# SSTuino_Evo.net
KiCad netlist of a schematic drawn in EAGLE
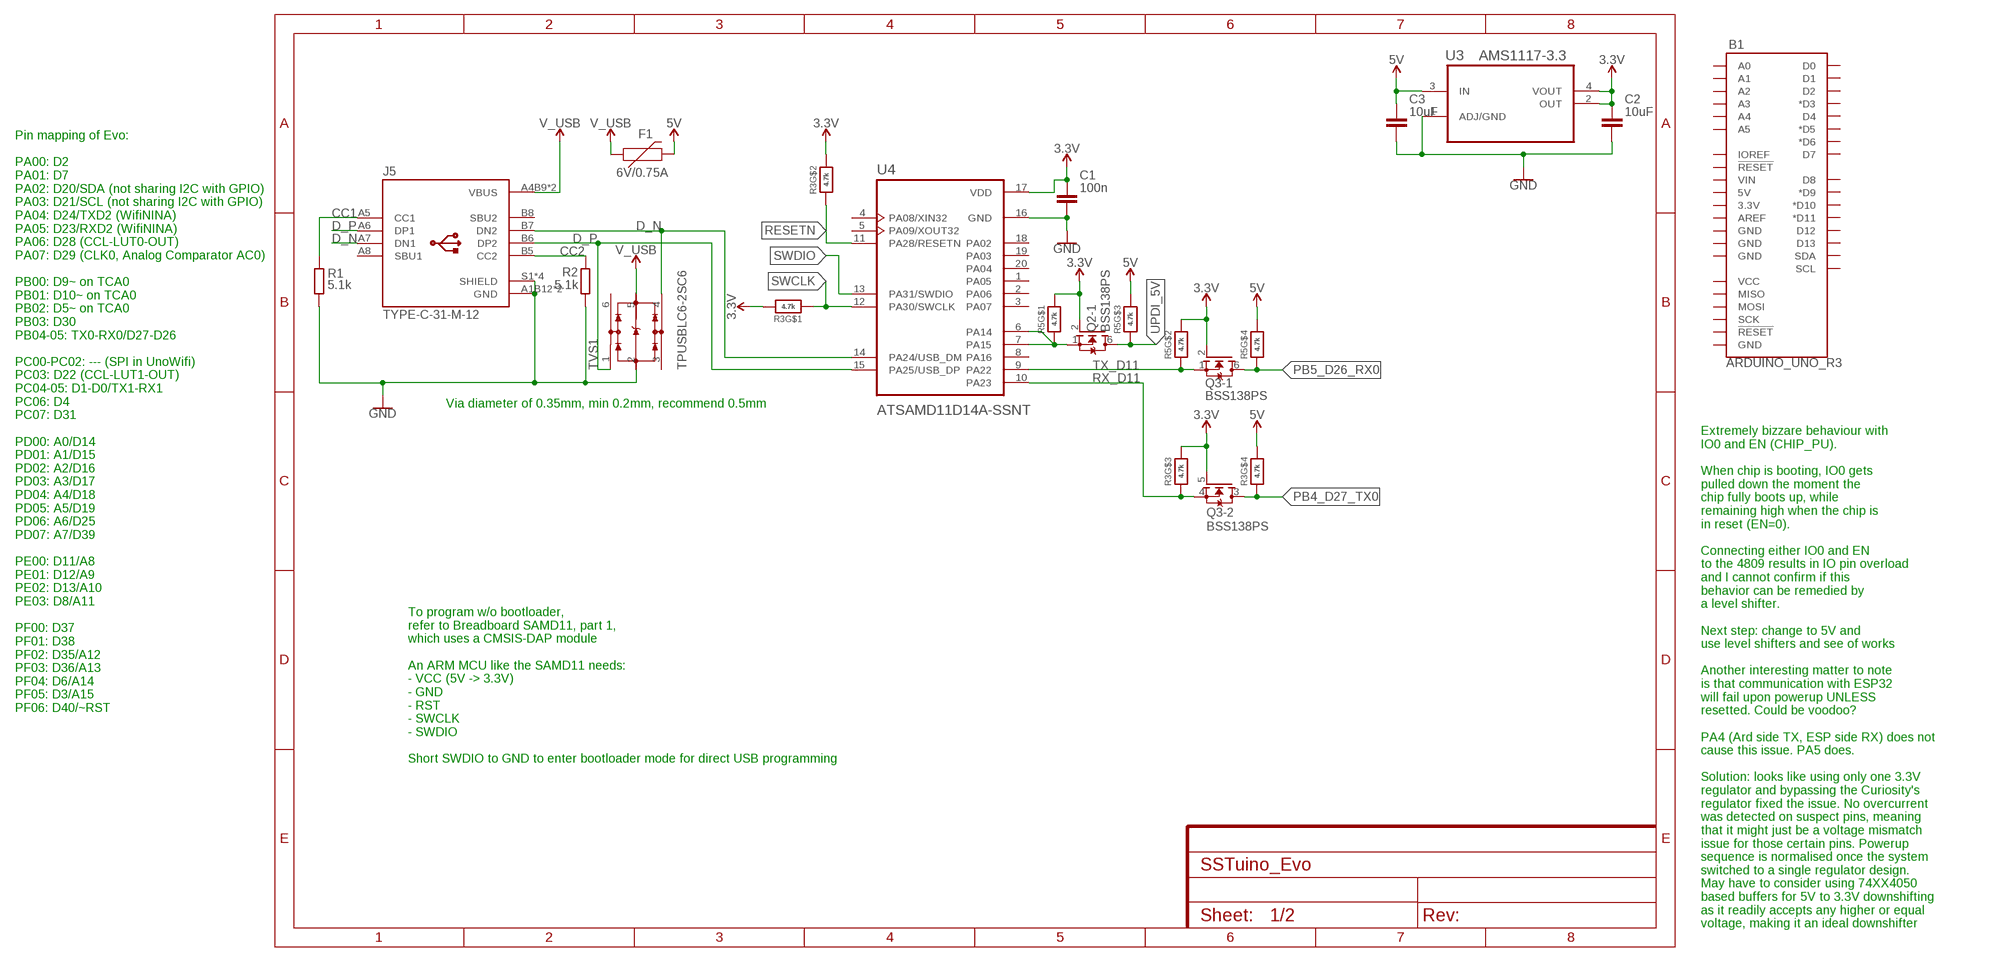
[diagram p0: schematic, sheet 1]
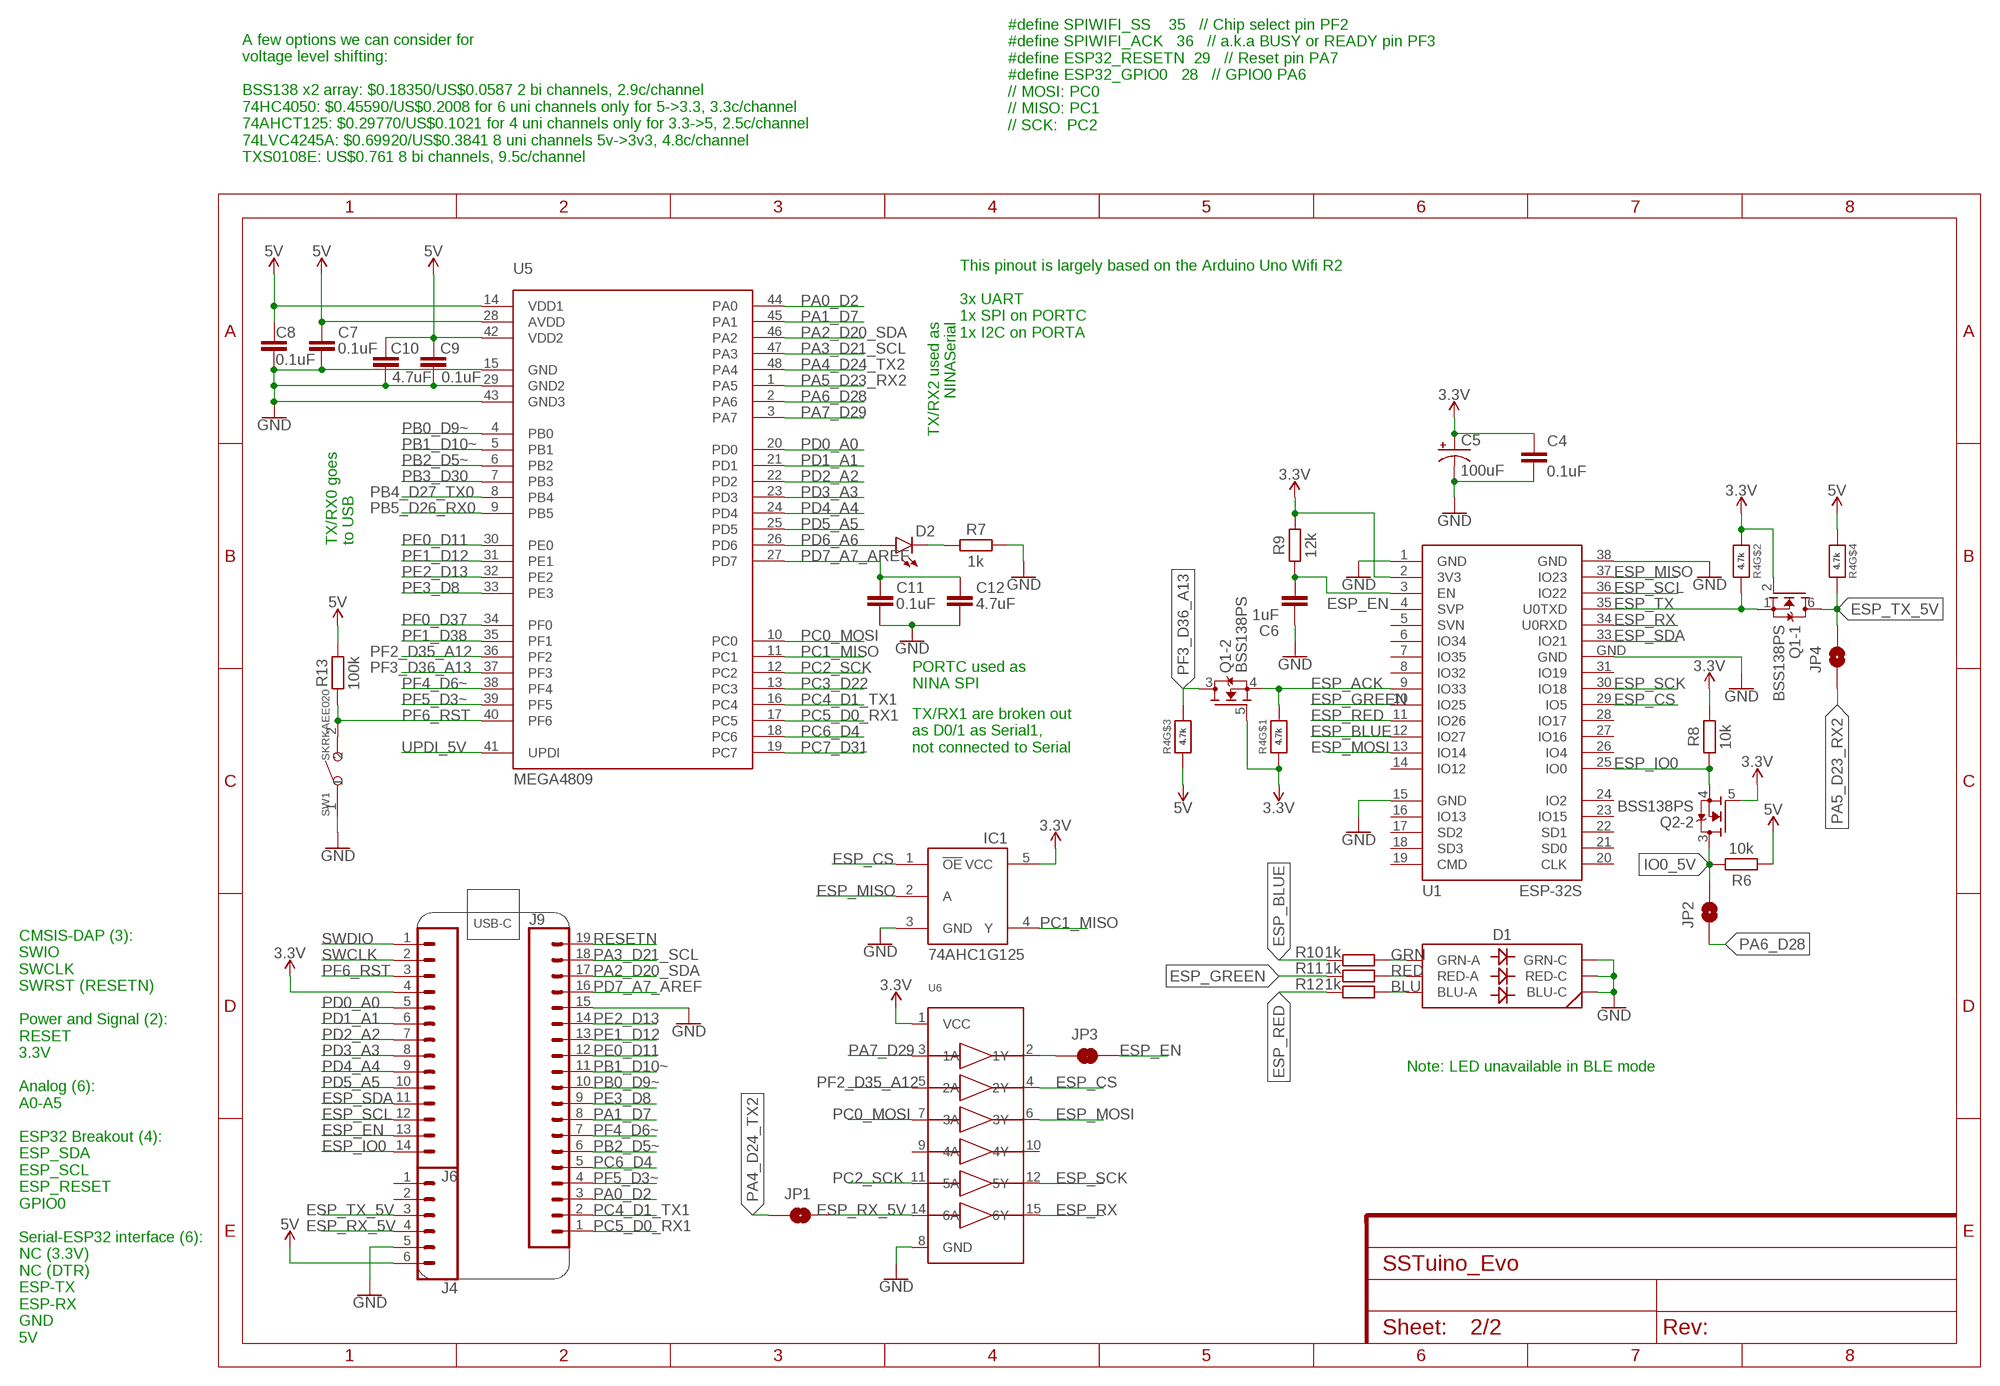
[diagram p1: schematic, sheet 2]

(export (version "E")
  (design (tool "Eeschema 10.0.6"))
  (components
    (comp (ref "C4")
      (value "0.1uF")
      (footprint "eagle-import:CAPC1005X60")
      (libsource (lib "eagle-import") (part "CCHIP-0402(1005-METRIC)_"))
    )
    (comp (ref "C5")
      (value "100uF")
      (footprint "eagle-import:CAPMP3216X180N")
      (libsource (lib "eagle-import") (part "C-POL-USTANTALUM-1206(3216-METRIC)_"))
    )
    (comp (ref "C6")
      (value "1uF")
      (footprint "eagle-import:CAPC1005X60")
      (libsource (lib "eagle-import") (part "CCHIP-0402(1005-METRIC)_"))
    )
    (comp (ref "C7")
      (value "0.1uF")
      (footprint "eagle-import:CAPC1005X60")
      (libsource (lib "eagle-import") (part "CCHIP-0402(1005-METRIC)_"))
    )
    (comp (ref "C8")
      (value "0.1uF")
      (footprint "eagle-import:CAPC1005X60")
      (libsource (lib "eagle-import") (part "CCHIP-0402(1005-METRIC)_"))
    )
    (comp (ref "C9")
      (value "0.1uF")
      (footprint "eagle-import:CAPC1005X60")
      (libsource (lib "eagle-import") (part "CCHIP-0402(1005-METRIC)_"))
    )
    (comp (ref "C10")
      (value "4.7uF")
      (footprint "eagle-import:CAPC1005X60")
      (libsource (lib "eagle-import") (part "CCHIP-0402(1005-METRIC)_"))
    )
    (comp (ref "C11")
      (value "0.1uF")
      (footprint "eagle-import:CAPC1005X60")
      (libsource (lib "eagle-import") (part "CCHIP-0402(1005-METRIC)_"))
    )
    (comp (ref "C12")
      (value "4.7uF")
      (footprint "eagle-import:CAPC1005X60")
      (libsource (lib "eagle-import") (part "CCHIP-0402(1005-METRIC)_"))
    )
    (comp (ref "D1")
      (value "LED-RGBTC5050RGBF08")
      (footprint "eagle-import:LED-TRICOLOR-5050")
      (libsource (lib "eagle-import") (part "LED-RGBTC5050RGBF08"))
    )
    (comp (ref "D2")
      (value "LED0603")
      (footprint "eagle-import:LED-0603")
      (libsource (lib "eagle-import") (part "LED0603"))
    )
    (comp (ref "IC1")
      (value "74AHC1G125")
      (footprint "eagle-import:SOT23-5L")
      (fields (field (name "LCSC_PART") "C124295"))
      (libsource (lib "eagle-import") (part "74AHC1G125"))
    )
    (comp (ref "J4")
      (value "CONN_06NO_SILK_FEMALE_PTH")
      (footprint "eagle-import:1X06_NO_SILK")
      (libsource (lib "eagle-import") (part "CONN_06NO_SILK_FEMALE_PTH"))
    )
    (comp (ref "J6")
      (value "CONN_14NO_SILK")
      (footprint "eagle-import:1X14_NO_SILK")
      (libsource (lib "eagle-import") (part "CONN_14NO_SILK"))
    )
    (comp (ref "J9")
      (value "CONN_191X19_NO_SILK")
      (footprint "eagle-import:1X19_NO_SILK")
      (libsource (lib "eagle-import") (part "CONN_191X19_NO_SILK"))
    )
    (comp (ref "JP1")
      (value "JUMPER-SMT_2_NO_SILK")
      (footprint "eagle-import:SMT-JUMPER_2_NO_SILK")
      (libsource (lib "eagle-import") (part "JUMPER-SMT_2_NO_SILK"))
    )
    (comp (ref "JP2")
      (value "JUMPER-SMT_2_NO_SILK")
      (footprint "eagle-import:SMT-JUMPER_2_NO_SILK")
      (libsource (lib "eagle-import") (part "JUMPER-SMT_2_NO_SILK"))
    )
    (comp (ref "JP3")
      (value "JUMPER-SMT_2_NC_TRACE_SILK")
      (footprint "eagle-import:SMT-JUMPER_2_NC_TRACE_SILK")
      (libsource (lib "eagle-import") (part "JUMPER-SMT_2_NC_TRACE_SILK"))
    )
    (comp (ref "JP4")
      (value "JUMPER-SMT_2_NO_SILK")
      (footprint "eagle-import:SMT-JUMPER_2_NO_SILK")
      (libsource (lib "eagle-import") (part "JUMPER-SMT_2_NO_SILK"))
    )
    (comp (ref "Q1")
      (value "BSS138PS")
      (footprint "eagle-import:ARDUINO-TRANSISTORS_SOT363")
      (fields (field (name "MANUFACTURER") "NXP") (field (name "LCSC_PART") "C193381"))
      (libsource (lib "eagle-import") (part "BSS138PS"))
    )
    (comp (ref "Q2")
      (value "BSS138PS")
      (footprint "eagle-import:ARDUINO-TRANSISTORS_SOT363")
      (fields (field (name "MANUFACTURER") "NXP") (field (name "LCSC_PART") "C193381"))
      (libsource (lib "eagle-import") (part "BSS138PS"))
    )
    (comp (ref "R4")
      (value "4.7k")
      (footprint "eagle-import:RESPACK_4X0402")
      (fields (field (name "LCSC_PART") "C1980"))
      (libsource (lib "eagle-import") (part "RESISTOR_4PACK0402"))
    )
    (comp (ref "R6")
      (value "10k")
      (footprint "eagle-import:RESC1005X40")
      (libsource (lib "eagle-import") (part "RCHIP-0402(1005-METRIC)_"))
    )
    (comp (ref "R7")
      (value "1k")
      (footprint "eagle-import:RESC1005X40")
      (libsource (lib "eagle-import") (part "RCHIP-0402(1005-METRIC)_"))
    )
    (comp (ref "R8")
      (value "10k")
      (footprint "eagle-import:RESC1005X40")
      (libsource (lib "eagle-import") (part "RCHIP-0402(1005-METRIC)_"))
    )
    (comp (ref "R9")
      (value "12k")
      (footprint "eagle-import:RESC1005X40")
      (libsource (lib "eagle-import") (part "RCHIP-0402(1005-METRIC)_"))
    )
    (comp (ref "R10")
      (value "1k")
      (footprint "eagle-import:RESC1005X40")
      (libsource (lib "eagle-import") (part "RCHIP-0402(1005-METRIC)_"))
    )
    (comp (ref "R11")
      (value "1k")
      (footprint "eagle-import:RESC1005X40")
      (libsource (lib "eagle-import") (part "RCHIP-0402(1005-METRIC)_"))
    )
    (comp (ref "R12")
      (value "1k")
      (footprint "eagle-import:RESC1005X40")
      (libsource (lib "eagle-import") (part "RCHIP-0402(1005-METRIC)_"))
    )
    (comp (ref "R13")
      (value "100k")
      (footprint "eagle-import:RESC1005X40")
      (libsource (lib "eagle-import") (part "RCHIP-0402(1005-METRIC)_"))
    )
    (comp (ref "SW1")
      (value "SKRKAEE020")
      (footprint "eagle-import:SW2-2.6-3.9X2.9X1.5+0.4MM")
      (fields (field (name "LCSC_PART") "C115357") (field (name "LCSC_PART_1") "C115357"))
      (libsource (lib "eagle-import") (part "SMD-BUTTON(2P-3.9X2.9X1.5+0.4MM)-SKRKAEE020"))
    )
    (comp (ref "U1")
      (value "ESP-32S")
      (footprint "eagle-import:ESP-32S")
      (libsource (lib "eagle-import") (part "ESP-32S"))
    )
    (comp (ref "U5")
      (value "MEGA4809")
      (footprint "eagle-import:TQFP48")
      (fields (field (name "LCSC_PART") "C189475"))
      (libsource (lib "eagle-import") (part "MEGA4809"))
    )
    (comp (ref "U6")
      (value "74HC4050DTSSOP")
      (footprint "eagle-import:TSSOP16")
      (fields (field (name "LCSC_PART") "C43181"))
      (libsource (lib "eagle-import") (part "74HC4050DTSSOP"))
    )
    (comp (ref "B1")
      (value "ARDUINO_UNO_R3")
      (footprint "eagle-import:ARDUINO_R3")
      (libsource (lib "eagle-import") (part "ARDUINO_UNO_R3"))
    )
    (comp (ref "C1")
      (value "100n")
      (footprint "eagle-import:CAPC1005X60")
      (libsource (lib "eagle-import") (part "CCHIP-0402(1005-METRIC)_"))
    )
    (comp (ref "C2")
      (value "10uF")
      (footprint "eagle-import:CAPC1608X85")
      (libsource (lib "eagle-import") (part "CCHIP-0603(1608-METRIC)_"))
    )
    (comp (ref "C3")
      (value "10uF")
      (footprint "eagle-import:CAPC1608X85")
      (libsource (lib "eagle-import") (part "CCHIP-0603(1608-METRIC)_"))
    )
    (comp (ref "F1")
      (value "6V/0.75A")
      (footprint "eagle-import:1206")
      (fields (field (name "LCSC_PART") "C99563"))
      (libsource (lib "eagle-import") (part "PPTC_THREE-QUARTER-AMP"))
    )
    (comp (ref "J5")
      (value "TYPE-C-31-M-12")
      (footprint "eagle-import:HRO_TYPE-C-31-M-12")
      (fields (field (name "MF") "HRO Electronics Co., Ltd.") (field (name "LCSC_PART") "C165948"))
      (libsource (lib "eagle-import") (part "TYPE-C-31-M-12"))
    )
    (comp (ref "Q3")
      (value "BSS138PS")
      (footprint "eagle-import:ARDUINO-TRANSISTORS_SOT363")
      (fields (field (name "MANUFACTURER") "NXP") (field (name "LCSC_PART") "C193381"))
      (libsource (lib "eagle-import") (part "BSS138PS"))
    )
    (comp (ref "R1")
      (value "5.1k")
      (footprint "eagle-import:RESC1005X40")
      (libsource (lib "eagle-import") (part "RCHIP-0402(1005-METRIC)_"))
    )
    (comp (ref "R2")
      (value "5.1k")
      (footprint "eagle-import:RESC1005X40")
      (libsource (lib "eagle-import") (part "RCHIP-0402(1005-METRIC)_"))
    )
    (comp (ref "R3")
      (value "4.7k")
      (footprint "eagle-import:RESPACK_4X0402")
      (fields (field (name "LCSC_PART") "C1980"))
      (libsource (lib "eagle-import") (part "RESISTOR_4PACK0402"))
    )
    (comp (ref "R5")
      (value "4.7k")
      (footprint "eagle-import:RESPACK_4X0402")
      (fields (field (name "LCSC_PART") "C1980"))
      (libsource (lib "eagle-import") (part "RESISTOR_4PACK0402"))
    )
    (comp (ref "TVS1")
      (value "TPUSBLC6-2SC6")
      (footprint "eagle-import:SOT95P280X110-6N")
      (fields (field (name "LCSC_PART") "C558442"))
      (libsource (lib "eagle-import") (part "TPUSBLC6-2SC6"))
    )
    (comp (ref "U3")
      (value "AMS1117-3.3")
      (footprint "eagle-import:SOT230P696X180-4N")
      (fields (field (name "MPN") "LM1117MP-3.3") (field (name "LCSC_PART") "C6186"))
      (libsource (lib "eagle-import") (part "LM1117MP-3.3"))
    )
    (comp (ref "U4")
      (value "ATSAMD11D14A-SSNT")
      (footprint "eagle-import:SOIC127P1030X265-20N")
      (fields (field (name "MF") "Microchip") (field (name "LCSC_PART") "C2053599"))
      (libsource (lib "eagle-import") (part "ATSAMD11D14A-SSNT"))
    )
  )
  (nets
    (net (code "1") (name "3.3V") (class "Default")
      (node (ref "C1") (pin "1") (pinfunction "1_1") (pintype "passive"))
      (node (ref "C2") (pin "1") (pinfunction "1_1") (pintype "passive"))
      (node (ref "C4") (pin "1") (pinfunction "1_1") (pintype "passive"))
      (node (ref "C5") (pin "1") (pinfunction "+_1") (pintype "passive"))
      (node (ref "IC1") (pin "5") (pinfunction "VCC_5") (pintype "power_in"))
      (node (ref "J6") (pin "4") (pinfunction "4_4") (pintype "passive"))
      (node (ref "Q1") (pin "2") (pinfunction "G_2") (pintype "passive"))
      (node (ref "Q1") (pin "5") (pinfunction "G_5") (pintype "passive"))
      (node (ref "Q2") (pin "2") (pinfunction "G_2") (pintype "passive"))
      (node (ref "Q2") (pin "5") (pinfunction "G_5") (pintype "passive"))
      (node (ref "Q3") (pin "2") (pinfunction "G_2") (pintype "passive"))
      (node (ref "Q3") (pin "5") (pinfunction "G_5") (pintype "passive"))
      (node (ref "R3") (pin "6") (pinfunction "2_6") (pintype "passive"))
      (node (ref "R3") (pin "7") (pinfunction "2_7") (pintype "passive"))
      (node (ref "R3") (pin "8") (pinfunction "2_8") (pintype "passive"))
      (node (ref "R4") (pin "1") (pinfunction "1_1") (pintype "passive"))
      (node (ref "R4") (pin "2") (pinfunction "1_2") (pintype "passive"))
      (node (ref "R5") (pin "7") (pinfunction "2_7") (pintype "passive"))
      (node (ref "R5") (pin "8") (pinfunction "2_8") (pintype "passive"))
      (node (ref "R8") (pin "2") (pinfunction "2_2") (pintype "passive"))
      (node (ref "R9") (pin "2") (pinfunction "2_2") (pintype "passive"))
      (node (ref "U1") (pin "2") (pinfunction "3V3_2") (pintype "power_in"))
      (node (ref "U3") (pin "2") (pinfunction "OUT_2") (pintype "output"))
      (node (ref "U3") (pin "4") (pinfunction "VOUT_4") (pintype "output"))
      (node (ref "U4") (pin "17") (pinfunction "VDD_17") (pintype "power_in"))
      (node (ref "U6") (pin "1") (pinfunction "VCC_1") (pintype "bidirectional"))
    )
    (net (code "2") (name "5V") (class "Default")
      (node (ref "C10") (pin "1") (pinfunction "1_1") (pintype "passive"))
      (node (ref "C3") (pin "1") (pinfunction "1_1") (pintype "passive"))
      (node (ref "C7") (pin "1") (pinfunction "1_1") (pintype "passive"))
      (node (ref "C8") (pin "1") (pinfunction "1_1") (pintype "passive"))
      (node (ref "C9") (pin "1") (pinfunction "1_1") (pintype "passive"))
      (node (ref "F1") (pin "2") (pinfunction "2_2") (pintype "bidirectional"))
      (node (ref "J4") (pin "6") (pinfunction "6_6") (pintype "passive"))
      (node (ref "R13") (pin "2") (pinfunction "2_2") (pintype "passive"))
      (node (ref "R3") (pin "5") (pinfunction "2_5") (pintype "passive"))
      (node (ref "R4") (pin "3") (pinfunction "1_3") (pintype "passive"))
      (node (ref "R4") (pin "4") (pinfunction "1_4") (pintype "passive"))
      (node (ref "R5") (pin "5") (pinfunction "2_5") (pintype "passive"))
      (node (ref "R5") (pin "6") (pinfunction "2_6") (pintype "passive"))
      (node (ref "R6") (pin "1") (pinfunction "1_1") (pintype "passive"))
      (node (ref "U3") (pin "3") (pinfunction "IN_3") (pintype "input"))
      (node (ref "U5") (pin "14") (pinfunction "VDD1_14") (pintype "bidirectional"))
      (node (ref "U5") (pin "28") (pinfunction "AVDD_28") (pintype "bidirectional"))
      (node (ref "U5") (pin "42") (pinfunction "VDD2_42") (pintype "bidirectional"))
    )
    (net (code "3") (name "BLU") (class "Default")
      (node (ref "D1") (pin "6") (pinfunction "BLU-A_6") (pintype "bidirectional"))
      (node (ref "R12") (pin "2") (pinfunction "2_2") (pintype "passive"))
    )
    (net (code "4") (name "CC1") (class "Default")
      (node (ref "J5") (pin "A5") (pinfunction "CC1_A5") (pintype "bidirectional"))
      (node (ref "R1") (pin "1") (pinfunction "1_1") (pintype "passive"))
    )
    (net (code "5") (name "CC2") (class "Default")
      (node (ref "J5") (pin "B5") (pinfunction "CC2_B5") (pintype "bidirectional"))
      (node (ref "R2") (pin "2") (pinfunction "2_2") (pintype "passive"))
    )
    (net (code "6") (name "D_N") (class "Default")
      (node (ref "J5") (pin "A7") (pinfunction "DN1_A7") (pintype "bidirectional"))
      (node (ref "J5") (pin "B7") (pinfunction "DN2_B7") (pintype "bidirectional"))
      (node (ref "TVS1") (pin "4") (pinfunction "IO3_4") (pintype "passive"))
      (node (ref "U4") (pin "14") (pinfunction "PA24/USB_DM_14") (pintype "bidirectional"))
    )
    (net (code "7") (name "D_P") (class "Default")
      (node (ref "J5") (pin "A6") (pinfunction "DP1_A6") (pintype "bidirectional"))
      (node (ref "J5") (pin "B6") (pinfunction "DP2_B6") (pintype "bidirectional"))
      (node (ref "TVS1") (pin "1") (pinfunction "IO1_1") (pintype "passive"))
      (node (ref "U4") (pin "15") (pinfunction "PA25/USB_DP_15") (pintype "bidirectional"))
    )
    (net (code "8") (name "ESP_ACK") (class "Default")
      (node (ref "Q1") (pin "4") (pinfunction "S_4") (pintype "passive"))
      (node (ref "R4") (pin "8") (pinfunction "2_8") (pintype "passive"))
      (node (ref "U1") (pin "9") (pinfunction "IO33_9") (pintype "bidirectional"))
    )
    (net (code "9") (name "ESP_BLUE") (class "Default")
      (node (ref "R10") (pin "1") (pinfunction "1_1") (pintype "passive"))
      (node (ref "U1") (pin "12") (pinfunction "IO27_12") (pintype "bidirectional"))
    )
    (net (code "10") (name "ESP_CS") (class "Default")
      (node (ref "IC1") (pin "1") (pinfunction "~{OE}_1") (pintype "input"))
      (node (ref "U1") (pin "29") (pinfunction "IO5_29") (pintype "bidirectional"))
      (node (ref "U6") (pin "4") (pinfunction "2Y_4") (pintype "bidirectional"))
    )
    (net (code "11") (name "ESP_EN") (class "Default")
      (node (ref "C6") (pin "2") (pinfunction "2_2") (pintype "passive"))
      (node (ref "J6") (pin "13") (pinfunction "13_13") (pintype "passive"))
      (node (ref "JP3") (pin "2") (pinfunction "2_2") (pintype "passive"))
      (node (ref "R9") (pin "1") (pinfunction "1_1") (pintype "passive"))
      (node (ref "U1") (pin "3") (pinfunction "EN_3") (pintype "input"))
    )
    (net (code "12") (name "ESP_GREEN") (class "Default")
      (node (ref "R11") (pin "1") (pinfunction "1_1") (pintype "passive"))
      (node (ref "U1") (pin "10") (pinfunction "IO25_10") (pintype "bidirectional"))
    )
    (net (code "13") (name "ESP_IO0") (class "Default")
      (node (ref "J6") (pin "14") (pinfunction "14_14") (pintype "passive"))
      (node (ref "Q2") (pin "4") (pinfunction "S_4") (pintype "passive"))
      (node (ref "R8") (pin "1") (pinfunction "1_1") (pintype "passive"))
      (node (ref "U1") (pin "25") (pinfunction "IO0_25") (pintype "bidirectional"))
    )
    (net (code "14") (name "ESP_MISO") (class "Default")
      (node (ref "IC1") (pin "2") (pinfunction "A_2") (pintype "input"))
      (node (ref "U1") (pin "37") (pinfunction "IO23_37") (pintype "bidirectional"))
    )
    (net (code "15") (name "ESP_MOSI") (class "Default")
      (node (ref "U1") (pin "13") (pinfunction "IO14_13") (pintype "bidirectional"))
      (node (ref "U6") (pin "6") (pinfunction "3Y_6") (pintype "bidirectional"))
    )
    (net (code "16") (name "ESP_RED") (class "Default")
      (node (ref "R12") (pin "1") (pinfunction "1_1") (pintype "passive"))
      (node (ref "U1") (pin "11") (pinfunction "IO26_11") (pintype "bidirectional"))
    )
    (net (code "17") (name "ESP_RX") (class "Default")
      (node (ref "U1") (pin "34") (pinfunction "U0RXD_34") (pintype "bidirectional"))
      (node (ref "U6") (pin "15") (pinfunction "6Y_15") (pintype "bidirectional"))
    )
    (net (code "18") (name "ESP_RX_5V") (class "Default")
      (node (ref "J4") (pin "4") (pinfunction "4_4") (pintype "passive"))
      (node (ref "JP1") (pin "2") (pinfunction "2_2") (pintype "passive"))
      (node (ref "U6") (pin "14") (pinfunction "6A_14") (pintype "bidirectional"))
    )
    (net (code "19") (name "ESP_SCK") (class "Default")
      (node (ref "U1") (pin "30") (pinfunction "IO18_30") (pintype "bidirectional"))
      (node (ref "U6") (pin "12") (pinfunction "5Y_12") (pintype "bidirectional"))
    )
    (net (code "20") (name "ESP_SCL") (class "Default")
      (node (ref "J6") (pin "12") (pinfunction "12_12") (pintype "passive"))
      (node (ref "U1") (pin "36") (pinfunction "IO22_36") (pintype "bidirectional"))
    )
    (net (code "21") (name "ESP_SDA") (class "Default")
      (node (ref "J6") (pin "11") (pinfunction "11_11") (pintype "passive"))
      (node (ref "U1") (pin "33") (pinfunction "IO21_33") (pintype "bidirectional"))
    )
    (net (code "22") (name "ESP_TX") (class "Default")
      (node (ref "Q1") (pin "1") (pinfunction "S_1") (pintype "passive"))
      (node (ref "R4") (pin "7") (pinfunction "2_7") (pintype "passive"))
      (node (ref "U1") (pin "35") (pinfunction "U0TXD_35") (pintype "bidirectional"))
    )
    (net (code "23") (name "ESP_TX_5V") (class "Default")
      (node (ref "J4") (pin "3") (pinfunction "3_3") (pintype "passive"))
      (node (ref "JP4") (pin "2") (pinfunction "2_2") (pintype "passive"))
      (node (ref "Q1") (pin "6") (pinfunction "D_6") (pintype "passive"))
      (node (ref "R4") (pin "5") (pinfunction "2_5") (pintype "passive"))
    )
    (net (code "24") (name "GND") (class "Default")
      (node (ref "C1") (pin "2") (pinfunction "2_2") (pintype "passive"))
      (node (ref "C10") (pin "2") (pinfunction "2_2") (pintype "passive"))
      (node (ref "C11") (pin "2") (pinfunction "2_2") (pintype "passive"))
      (node (ref "C12") (pin "2") (pinfunction "2_2") (pintype "passive"))
      (node (ref "C2") (pin "2") (pinfunction "2_2") (pintype "passive"))
      (node (ref "C3") (pin "2") (pinfunction "2_2") (pintype "passive"))
      (node (ref "C4") (pin "2") (pinfunction "2_2") (pintype "passive"))
      (node (ref "C5") (pin "2") (pinfunction "-_2") (pintype "passive"))
      (node (ref "C6") (pin "1") (pinfunction "1_1") (pintype "passive"))
      (node (ref "C7") (pin "2") (pinfunction "2_2") (pintype "passive"))
      (node (ref "C8") (pin "2") (pinfunction "2_2") (pintype "passive"))
      (node (ref "C9") (pin "2") (pinfunction "2_2") (pintype "passive"))
      (node (ref "D1") (pin "1") (pinfunction "BLU-C_1") (pintype "bidirectional"))
      (node (ref "D1") (pin "2") (pinfunction "RED-C_2") (pintype "bidirectional"))
      (node (ref "D1") (pin "3") (pinfunction "GRN-C_3") (pintype "bidirectional"))
      (node (ref "IC1") (pin "3") (pinfunction "GND_3") (pintype "power_in"))
      (node (ref "J4") (pin "5") (pinfunction "5_5") (pintype "passive"))
      (node (ref "J5") (pin "A1B12") (pinfunction "GND_A1B12") (pintype "power_in"))
      (node (ref "J5") (pin "B1A12") (pinfunction "GND_B1A12") (pintype "power_in"))
      (node (ref "J5") (pin "S1") (pinfunction "SHIELD_S1") (pintype "passive"))
      (node (ref "J5") (pin "S2") (pinfunction "SHIELD_S2") (pintype "passive"))
      (node (ref "J5") (pin "S3") (pinfunction "SHIELD_S3") (pintype "passive"))
      (node (ref "J5") (pin "S4") (pinfunction "SHIELD_S4") (pintype "passive"))
      (node (ref "J9") (pin "15") (pinfunction "15_15") (pintype "passive"))
      (node (ref "R1") (pin "2") (pinfunction "2_2") (pintype "passive"))
      (node (ref "R2") (pin "1") (pinfunction "1_1") (pintype "passive"))
      (node (ref "R7") (pin "2") (pinfunction "2_2") (pintype "passive"))
      (node (ref "SW1") (pin "1") (pinfunction "1_1") (pintype "bidirectional"))
      (node (ref "TVS1") (pin "2") (pinfunction "VSS_2") (pintype "power_in"))
      (node (ref "U1") (pin "1") (pinfunction "GND_1") (pintype "power_in"))
      (node (ref "U1") (pin "15") (pinfunction "GND_15") (pintype "power_in"))
      (node (ref "U1") (pin "38") (pinfunction "GND_38") (pintype "power_in"))
      (node (ref "U1") (pin "GND") (pinfunction "GND_GND") (pintype "power_in"))
      (node (ref "U3") (pin "1") (pinfunction "ADJ/GND_1") (pintype "passive"))
      (node (ref "U4") (pin "16") (pinfunction "GND_16") (pintype "power_in"))
      (node (ref "U5") (pin "15") (pinfunction "GND_15") (pintype "bidirectional"))
      (node (ref "U5") (pin "29") (pinfunction "GND2_29") (pintype "bidirectional"))
      (node (ref "U5") (pin "43") (pinfunction "GND3_43") (pintype "bidirectional"))
      (node (ref "U6") (pin "8") (pinfunction "GND_8") (pintype "bidirectional"))
    )
    (net (code "25") (name "GRN") (class "Default")
      (node (ref "D1") (pin "4") (pinfunction "GRN-A_4") (pintype "bidirectional"))
      (node (ref "R10") (pin "2") (pinfunction "2_2") (pintype "passive"))
    )
    (net (code "26") (name "IO0_5V") (class "Default")
      (node (ref "JP2") (pin "2") (pinfunction "2_2") (pintype "passive"))
      (node (ref "Q2") (pin "3") (pinfunction "D_3") (pintype "passive"))
      (node (ref "R6") (pin "2") (pinfunction "2_2") (pintype "passive"))
    )
    (net (code "27") (name "Net-(D2-PadC)") (class "Default")
      (node (ref "D2") (pin "C") (pinfunction "C_C") (pintype "passive"))
      (node (ref "R7") (pin "1") (pinfunction "1_1") (pintype "passive"))
    )
    (net (code "28") (name "Net-(Q2A-S)") (class "Default")
      (node (ref "Q2") (pin "1") (pinfunction "S_1") (pintype "passive"))
      (node (ref "R5") (pin "1") (pinfunction "1_1") (pintype "passive"))
      (node (ref "U4") (pin "6") (pinfunction "PA14_6") (pintype "bidirectional"))
      (node (ref "U4") (pin "7") (pinfunction "PA15_7") (pintype "bidirectional"))
    )
    (net (code "29") (name "Net-(U6-1Y)") (class "Default")
      (node (ref "JP3") (pin "1") (pinfunction "1_1") (pintype "passive"))
      (node (ref "U6") (pin "2") (pinfunction "1Y_2") (pintype "bidirectional"))
    )
    (net (code "30") (name "PA0_D2") (class "Default")
      (node (ref "J9") (pin "3") (pinfunction "3_3") (pintype "passive"))
      (node (ref "U5") (pin "44") (pinfunction "PA0_44") (pintype "bidirectional"))
    )
    (net (code "31") (name "PA1_D7") (class "Default")
      (node (ref "J9") (pin "8") (pinfunction "8_8") (pintype "passive"))
      (node (ref "U5") (pin "45") (pinfunction "PA1_45") (pintype "bidirectional"))
    )
    (net (code "32") (name "PA2_D20_SDA") (class "Default")
      (node (ref "J9") (pin "17") (pinfunction "17_17") (pintype "passive"))
      (node (ref "U5") (pin "46") (pinfunction "PA2_46") (pintype "bidirectional"))
    )
    (net (code "33") (name "PA3_D21_SCL") (class "Default")
      (node (ref "J9") (pin "18") (pinfunction "18_18") (pintype "passive"))
      (node (ref "U5") (pin "47") (pinfunction "PA3_47") (pintype "bidirectional"))
    )
    (net (code "34") (name "PA4_D24_TX2") (class "Default")
      (node (ref "JP1") (pin "1") (pinfunction "1_1") (pintype "passive"))
      (node (ref "U5") (pin "48") (pinfunction "PA4_48") (pintype "bidirectional"))
    )
    (net (code "35") (name "PA5_D23_RX2") (class "Default")
      (node (ref "JP4") (pin "1") (pinfunction "1_1") (pintype "passive"))
      (node (ref "U5") (pin "1") (pinfunction "PA5_1") (pintype "bidirectional"))
    )
    (net (code "36") (name "PA6_D28") (class "Default")
      (node (ref "JP2") (pin "1") (pinfunction "1_1") (pintype "passive"))
      (node (ref "U5") (pin "2") (pinfunction "PA6_2") (pintype "bidirectional"))
    )
    (net (code "37") (name "PA7_D29") (class "Default")
      (node (ref "U5") (pin "3") (pinfunction "PA7_3") (pintype "bidirectional"))
      (node (ref "U6") (pin "3") (pinfunction "1A_3") (pintype "bidirectional"))
    )
    (net (code "38") (name "PB0_D9~{}") (class "Default")
      (node (ref "J9") (pin "10") (pinfunction "10_10") (pintype "passive"))
      (node (ref "U5") (pin "4") (pinfunction "PB0_4") (pintype "bidirectional"))
    )
    (net (code "39") (name "PB1_D10~{}") (class "Default")
      (node (ref "J9") (pin "11") (pinfunction "11_11") (pintype "passive"))
      (node (ref "U5") (pin "5") (pinfunction "PB1_5") (pintype "bidirectional"))
    )
    (net (code "40") (name "PB2_D5~{}") (class "Default")
      (node (ref "J9") (pin "6") (pinfunction "6_6") (pintype "passive"))
      (node (ref "U5") (pin "6") (pinfunction "PB2_6") (pintype "bidirectional"))
    )
    (net (code "41") (name "PB3_D30") (class "Default")
      (node (ref "U5") (pin "7") (pinfunction "PB3_7") (pintype "bidirectional"))
    )
    (net (code "42") (name "PB4_D27_TX0") (class "Default")
      (node (ref "Q3") (pin "3") (pinfunction "D_3") (pintype "passive"))
      (node (ref "R3") (pin "4") (pinfunction "1_4") (pintype "passive"))
      (node (ref "U5") (pin "8") (pinfunction "PB4_8") (pintype "bidirectional"))
    )
    (net (code "43") (name "PB5_D26_RX0") (class "Default")
      (node (ref "Q3") (pin "6") (pinfunction "D_6") (pintype "passive"))
      (node (ref "R5") (pin "4") (pinfunction "1_4") (pintype "passive"))
      (node (ref "U5") (pin "9") (pinfunction "PB5_9") (pintype "bidirectional"))
    )
    (net (code "44") (name "PC0_MOSI") (class "Default")
      (node (ref "U5") (pin "10") (pinfunction "PC0_10") (pintype "bidirectional"))
      (node (ref "U6") (pin "7") (pinfunction "3A_7") (pintype "bidirectional"))
    )
    (net (code "45") (name "PC1_MISO") (class "Default")
      (node (ref "IC1") (pin "4") (pinfunction "Y_4") (pintype "output"))
      (node (ref "U5") (pin "11") (pinfunction "PC1_11") (pintype "bidirectional"))
    )
    (net (code "46") (name "PC2_SCK") (class "Default")
      (node (ref "U5") (pin "12") (pinfunction "PC2_12") (pintype "bidirectional"))
      (node (ref "U6") (pin "11") (pinfunction "5A_11") (pintype "bidirectional"))
    )
    (net (code "47") (name "PC3_D22") (class "Default")
      (node (ref "U5") (pin "13") (pinfunction "PC3_13") (pintype "bidirectional"))
    )
    (net (code "48") (name "PC4_D1_TX1") (class "Default")
      (node (ref "J9") (pin "2") (pinfunction "2_2") (pintype "passive"))
      (node (ref "U5") (pin "16") (pinfunction "PC4_16") (pintype "bidirectional"))
    )
    (net (code "49") (name "PC5_D0_RX1") (class "Default")
      (node (ref "J9") (pin "1") (pinfunction "1_1") (pintype "passive"))
      (node (ref "U5") (pin "17") (pinfunction "PC5_17") (pintype "bidirectional"))
    )
    (net (code "50") (name "PC6_D4") (class "Default")
      (node (ref "J9") (pin "5") (pinfunction "5_5") (pintype "passive"))
      (node (ref "U5") (pin "18") (pinfunction "PC6_18") (pintype "bidirectional"))
    )
    (net (code "51") (name "PC7_D31") (class "Default")
      (node (ref "U5") (pin "19") (pinfunction "PC7_19") (pintype "bidirectional"))
    )
    (net (code "52") (name "PD0_A0") (class "Default")
      (node (ref "J6") (pin "5") (pinfunction "5_5") (pintype "passive"))
      (node (ref "U5") (pin "20") (pinfunction "PD0_20") (pintype "bidirectional"))
    )
    (net (code "53") (name "PD1_A1") (class "Default")
      (node (ref "J6") (pin "6") (pinfunction "6_6") (pintype "passive"))
      (node (ref "U5") (pin "21") (pinfunction "PD1_21") (pintype "bidirectional"))
    )
    (net (code "54") (name "PD2_A2") (class "Default")
      (node (ref "J6") (pin "7") (pinfunction "7_7") (pintype "passive"))
      (node (ref "U5") (pin "22") (pinfunction "PD2_22") (pintype "bidirectional"))
    )
    (net (code "55") (name "PD3_A3") (class "Default")
      (node (ref "J6") (pin "8") (pinfunction "8_8") (pintype "passive"))
      (node (ref "U5") (pin "23") (pinfunction "PD3_23") (pintype "bidirectional"))
    )
    (net (code "56") (name "PD4_A4") (class "Default")
      (node (ref "J6") (pin "9") (pinfunction "9_9") (pintype "passive"))
      (node (ref "U5") (pin "24") (pinfunction "PD4_24") (pintype "bidirectional"))
    )
    (net (code "57") (name "PD5_A5") (class "Default")
      (node (ref "J6") (pin "10") (pinfunction "10_10") (pintype "passive"))
      (node (ref "U5") (pin "25") (pinfunction "PD5_25") (pintype "bidirectional"))
    )
    (net (code "58") (name "PD6_A6") (class "Default")
      (node (ref "D2") (pin "A") (pinfunction "A_A") (pintype "passive"))
      (node (ref "U5") (pin "26") (pinfunction "PD6_26") (pintype "bidirectional"))
    )
    (net (code "59") (name "PD7_A7_AREF") (class "Default")
      (node (ref "C11") (pin "1") (pinfunction "1_1") (pintype "passive"))
      (node (ref "C12") (pin "1") (pinfunction "1_1") (pintype "passive"))
      (node (ref "J9") (pin "16") (pinfunction "16_16") (pintype "passive"))
      (node (ref "U5") (pin "27") (pinfunction "PD7_27") (pintype "bidirectional"))
    )
    (net (code "60") (name "PE0_D11") (class "Default")
      (node (ref "J9") (pin "12") (pinfunction "12_12") (pintype "passive"))
      (node (ref "U5") (pin "30") (pinfunction "PE0_30") (pintype "bidirectional"))
    )
    (net (code "61") (name "PE1_D12") (class "Default")
      (node (ref "J9") (pin "13") (pinfunction "13_13") (pintype "passive"))
      (node (ref "U5") (pin "31") (pinfunction "PE1_31") (pintype "bidirectional"))
    )
    (net (code "62") (name "PE2_D13") (class "Default")
      (node (ref "J9") (pin "14") (pinfunction "14_14") (pintype "passive"))
      (node (ref "U5") (pin "32") (pinfunction "PE2_32") (pintype "bidirectional"))
    )
    (net (code "63") (name "PE3_D8") (class "Default")
      (node (ref "J9") (pin "9") (pinfunction "9_9") (pintype "passive"))
      (node (ref "U5") (pin "33") (pinfunction "PE3_33") (pintype "bidirectional"))
    )
    (net (code "64") (name "PF0_D37") (class "Default")
      (node (ref "U5") (pin "34") (pinfunction "PF0_34") (pintype "bidirectional"))
    )
    (net (code "65") (name "PF1_D38") (class "Default")
      (node (ref "U5") (pin "35") (pinfunction "PF1_35") (pintype "bidirectional"))
    )
    (net (code "66") (name "PF2_D35_A12") (class "Default")
      (node (ref "U5") (pin "36") (pinfunction "PF2_36") (pintype "bidirectional"))
      (node (ref "U6") (pin "5") (pinfunction "2A_5") (pintype "bidirectional"))
    )
    (net (code "67") (name "PF3_D36_A13") (class "Default")
      (node (ref "Q1") (pin "3") (pinfunction "D_3") (pintype "passive"))
      (node (ref "R4") (pin "6") (pinfunction "2_6") (pintype "passive"))
      (node (ref "U5") (pin "37") (pinfunction "PF3_37") (pintype "bidirectional"))
    )
    (net (code "68") (name "PF4_D6~{}") (class "Default")
      (node (ref "J9") (pin "7") (pinfunction "7_7") (pintype "passive"))
      (node (ref "U5") (pin "38") (pinfunction "PF4_38") (pintype "bidirectional"))
    )
    (net (code "69") (name "PF5_D3~{}") (class "Default")
      (node (ref "J9") (pin "4") (pinfunction "4_4") (pintype "passive"))
      (node (ref "U5") (pin "39") (pinfunction "PF5_39") (pintype "bidirectional"))
    )
    (net (code "70") (name "PF6_RST") (class "Default")
      (node (ref "J6") (pin "3") (pinfunction "3_3") (pintype "passive"))
      (node (ref "R13") (pin "1") (pinfunction "1_1") (pintype "passive"))
      (node (ref "SW1") (pin "2") (pinfunction "2_2") (pintype "bidirectional"))
      (node (ref "U5") (pin "40") (pinfunction "PF6_40") (pintype "bidirectional"))
    )
    (net (code "71") (name "RED") (class "Default")
      (node (ref "D1") (pin "5") (pinfunction "RED-A_5") (pintype "bidirectional"))
      (node (ref "R11") (pin "2") (pinfunction "2_2") (pintype "passive"))
    )
    (net (code "72") (name "RESETN") (class "Default")
      (node (ref "J9") (pin "19") (pinfunction "19_19") (pintype "passive"))
      (node (ref "R3") (pin "2") (pinfunction "1_2") (pintype "passive"))
      (node (ref "U4") (pin "11") (pinfunction "PA28/RESETN_11") (pintype "input"))
    )
    (net (code "73") (name "RX_D11") (class "Default")
      (node (ref "Q3") (pin "4") (pinfunction "S_4") (pintype "passive"))
      (node (ref "R3") (pin "3") (pinfunction "1_3") (pintype "passive"))
      (node (ref "U4") (pin "10") (pinfunction "PA23_10") (pintype "bidirectional"))
    )
    (net (code "74") (name "SWCLK") (class "Default")
      (node (ref "J6") (pin "2") (pinfunction "2_2") (pintype "passive"))
      (node (ref "R3") (pin "1") (pinfunction "1_1") (pintype "passive"))
      (node (ref "U4") (pin "12") (pinfunction "PA30/SWCLK_12") (pintype "bidirectional"))
    )
    (net (code "75") (name "SWDIO") (class "Default")
      (node (ref "J6") (pin "1") (pinfunction "1_1") (pintype "passive"))
      (node (ref "U4") (pin "13") (pinfunction "PA31/SWDIO_13") (pintype "bidirectional"))
    )
    (net (code "76") (name "TX_D11") (class "Default")
      (node (ref "Q3") (pin "1") (pinfunction "S_1") (pintype "passive"))
      (node (ref "R5") (pin "2") (pinfunction "1_2") (pintype "passive"))
      (node (ref "U4") (pin "9") (pinfunction "PA22_9") (pintype "bidirectional"))
    )
    (net (code "77") (name "UPDI_5V") (class "Default")
      (node (ref "Q2") (pin "6") (pinfunction "D_6") (pintype "passive"))
      (node (ref "R5") (pin "3") (pinfunction "1_3") (pintype "passive"))
      (node (ref "U5") (pin "41") (pinfunction "UPDI_41") (pintype "bidirectional"))
    )
    (net (code "78") (name "V_USB") (class "Default")
      (node (ref "F1") (pin "1") (pinfunction "1_1") (pintype "bidirectional"))
      (node (ref "J5") (pin "A4B9") (pinfunction "VBUS_A4B9") (pintype "power_in"))
      (node (ref "J5") (pin "B4A9") (pinfunction "VBUS_B4A9") (pintype "power_in"))
      (node (ref "TVS1") (pin "5") (pinfunction "VCC_5") (pintype "power_in"))
    )
    (net (code "79") (name "unconnected-(B1-*D3-PadD3)") (class "Default")
      (node (ref "B1") (pin "D3") (pinfunction "*D3_D3") (pintype "bidirectional"))
    )
    (net (code "80") (name "unconnected-(B1-*D5-PadD5)") (class "Default")
      (node (ref "B1") (pin "D5") (pinfunction "*D5_D5") (pintype "bidirectional"))
    )
    (net (code "81") (name "unconnected-(B1-*D6-PadD6)") (class "Default")
      (node (ref "B1") (pin "D6") (pinfunction "*D6_D6") (pintype "bidirectional"))
    )
    (net (code "82") (name "unconnected-(B1-*D9-PadD9)") (class "Default")
      (node (ref "B1") (pin "D9") (pinfunction "*D9_D9") (pintype "bidirectional"))
    )
    (net (code "83") (name "unconnected-(B1-*D10-PadD10)") (class "Default")
      (node (ref "B1") (pin "D10") (pinfunction "*D10_D10") (pintype "bidirectional"))
    )
    (net (code "84") (name "unconnected-(B1-*D11-PadD11)") (class "Default")
      (node (ref "B1") (pin "D11") (pinfunction "*D11_D11") (pintype "bidirectional"))
    )
    (net (code "85") (name "unconnected-(B1-GND-PadGND@1)") (class "Default")
      (node (ref "B1") (pin "GND@1") (pinfunction "GND_GND@1") (pintype "bidirectional"))
    )
    (net (code "86") (name "unconnected-(B1-GND-PadGND@2)") (class "Default")
      (node (ref "B1") (pin "GND@2") (pinfunction "GND_GND@2") (pintype "bidirectional"))
    )
    (net (code "87") (name "unconnected-(B1-GND-PadGND@3)") (class "Default")
      (node (ref "B1") (pin "GND@3") (pinfunction "GND_GND@3") (pintype "bidirectional"))
    )
    (net (code "88") (name "unconnected-(B1-GND-PadGND@4)") (class "Default")
      (node (ref "B1") (pin "GND@4") (pinfunction "GND_GND@4") (pintype "bidirectional"))
    )
    (net (code "89") (name "unconnected-(B1-Pad3.3V)") (class "Default")
      (node (ref "B1") (pin "3.3V") (pinfunction "3.3V_3.3V") (pintype "bidirectional"))
    )
    (net (code "90") (name "unconnected-(B1-Pad5V)") (class "Default")
      (node (ref "B1") (pin "5V") (pinfunction "5V_5V") (pintype "bidirectional"))
    )
    (net (code "91") (name "unconnected-(B1-PadA0)") (class "Default")
      (node (ref "B1") (pin "A0") (pinfunction "A0_A0") (pintype "bidirectional"))
    )
    (net (code "92") (name "unconnected-(B1-PadA1)") (class "Default")
      (node (ref "B1") (pin "A1") (pinfunction "A1_A1") (pintype "bidirectional"))
    )
    (net (code "93") (name "unconnected-(B1-PadA2)") (class "Default")
      (node (ref "B1") (pin "A2") (pinfunction "A2_A2") (pintype "bidirectional"))
    )
    (net (code "94") (name "unconnected-(B1-PadA3)") (class "Default")
      (node (ref "B1") (pin "A3") (pinfunction "A3_A3") (pintype "bidirectional"))
    )
    (net (code "95") (name "unconnected-(B1-PadA4)") (class "Default")
      (node (ref "B1") (pin "A4") (pinfunction "A4_A4") (pintype "bidirectional"))
    )
    (net (code "96") (name "unconnected-(B1-PadA5)") (class "Default")
      (node (ref "B1") (pin "A5") (pinfunction "A5_A5") (pintype "bidirectional"))
    )
    (net (code "97") (name "unconnected-(B1-PadAREF)") (class "Default")
      (node (ref "B1") (pin "AREF") (pinfunction "AREF_AREF") (pintype "bidirectional"))
    )
    (net (code "98") (name "unconnected-(B1-PadD0)") (class "Default")
      (node (ref "B1") (pin "D0") (pinfunction "D0_D0") (pintype "bidirectional"))
    )
    (net (code "99") (name "unconnected-(B1-PadD1)") (class "Default")
      (node (ref "B1") (pin "D1") (pinfunction "D1_D1") (pintype "bidirectional"))
    )
    (net (code "100") (name "unconnected-(B1-PadD2)") (class "Default")
      (node (ref "B1") (pin "D2") (pinfunction "D2_D2") (pintype "bidirectional"))
    )
    (net (code "101") (name "unconnected-(B1-PadD4)") (class "Default")
      (node (ref "B1") (pin "D4") (pinfunction "D4_D4") (pintype "bidirectional"))
    )
    (net (code "102") (name "unconnected-(B1-PadD7)") (class "Default")
      (node (ref "B1") (pin "D7") (pinfunction "D7_D7") (pintype "bidirectional"))
    )
    (net (code "103") (name "unconnected-(B1-PadD8)") (class "Default")
      (node (ref "B1") (pin "D8") (pinfunction "D8_D8") (pintype "bidirectional"))
    )
    (net (code "104") (name "unconnected-(B1-PadD12)") (class "Default")
      (node (ref "B1") (pin "D12") (pinfunction "D12_D12") (pintype "bidirectional"))
    )
    (net (code "105") (name "unconnected-(B1-PadD13)") (class "Default")
      (node (ref "B1") (pin "D13") (pinfunction "D13_D13") (pintype "bidirectional"))
    )
    (net (code "106") (name "unconnected-(B1-PadIOREF)") (class "Default")
      (node (ref "B1") (pin "IOREF") (pinfunction "IOREF_IOREF") (pintype "bidirectional"))
    )
    (net (code "107") (name "unconnected-(B1-PadMISO)") (class "Default")
      (node (ref "B1") (pin "MISO") (pinfunction "MISO_MISO") (pintype "bidirectional"))
    )
    (net (code "108") (name "unconnected-(B1-PadMOSI)") (class "Default")
      (node (ref "B1") (pin "MOSI") (pinfunction "MOSI_MOSI") (pintype "bidirectional"))
    )
    (net (code "109") (name "unconnected-(B1-PadSCK)") (class "Default")
      (node (ref "B1") (pin "SCK") (pinfunction "SCK_SCK") (pintype "bidirectional"))
    )
    (net (code "110") (name "unconnected-(B1-PadSCL)") (class "Default")
      (node (ref "B1") (pin "SCL") (pinfunction "SCL_SCL") (pintype "bidirectional"))
    )
    (net (code "111") (name "unconnected-(B1-PadSDA)") (class "Default")
      (node (ref "B1") (pin "SDA") (pinfunction "SDA_SDA") (pintype "bidirectional"))
    )
    (net (code "112") (name "unconnected-(B1-PadVCC)") (class "Default")
      (node (ref "B1") (pin "VCC") (pinfunction "VCC_VCC") (pintype "bidirectional"))
    )
    (net (code "113") (name "unconnected-(B1-PadVIN)") (class "Default")
      (node (ref "B1") (pin "VIN") (pinfunction "VIN_VIN") (pintype "bidirectional"))
    )
    (net (code "114") (name "unconnected-(B1-~{RESET}-PadRESET@1)") (class "Default")
      (node (ref "B1") (pin "RESET@1") (pinfunction "~{RESET}_RESET@1") (pintype "bidirectional"))
    )
    (net (code "115") (name "unconnected-(B1-~{RESET}-PadRESET@2)") (class "Default")
      (node (ref "B1") (pin "RESET@2") (pinfunction "~{RESET}_RESET@2") (pintype "bidirectional"))
    )
    (net (code "116") (name "unconnected-(J4-Pad1)") (class "Default")
      (node (ref "J4") (pin "1") (pinfunction "1_1") (pintype "passive"))
    )
    (net (code "117") (name "unconnected-(J4-Pad2)") (class "Default")
      (node (ref "J4") (pin "2") (pinfunction "2_2") (pintype "passive"))
    )
    (net (code "118") (name "unconnected-(J5-SBU1-PadA8)") (class "Default")
      (node (ref "J5") (pin "A8") (pinfunction "SBU1_A8") (pintype "bidirectional"))
    )
    (net (code "119") (name "unconnected-(J5-SBU2-PadB8)") (class "Default")
      (node (ref "J5") (pin "B8") (pinfunction "SBU2_B8") (pintype "bidirectional"))
    )
    (net (code "120") (name "unconnected-(TVS1-IO2-Pad3)") (class "Default")
      (node (ref "TVS1") (pin "3") (pinfunction "IO2_3") (pintype "passive"))
    )
    (net (code "121") (name "unconnected-(TVS1-IO4-Pad6)") (class "Default")
      (node (ref "TVS1") (pin "6") (pinfunction "IO4_6") (pintype "passive"))
    )
    (net (code "122") (name "unconnected-(U1-CLK-Pad20)") (class "Default")
      (node (ref "U1") (pin "20") (pinfunction "CLK_20") (pintype "bidirectional"))
    )
    (net (code "123") (name "unconnected-(U1-CMD-Pad19)") (class "Default")
      (node (ref "U1") (pin "19") (pinfunction "CMD_19") (pintype "bidirectional"))
    )
    (net (code "124") (name "unconnected-(U1-IO2-Pad24)") (class "Default")
      (node (ref "U1") (pin "24") (pinfunction "IO2_24") (pintype "bidirectional"))
    )
    (net (code "125") (name "unconnected-(U1-IO4-Pad26)") (class "Default")
      (node (ref "U1") (pin "26") (pinfunction "IO4_26") (pintype "bidirectional"))
    )
    (net (code "126") (name "unconnected-(U1-IO12-Pad14)") (class "Default")
      (node (ref "U1") (pin "14") (pinfunction "IO12_14") (pintype "bidirectional"))
    )
    (net (code "127") (name "unconnected-(U1-IO13-Pad16)") (class "Default")
      (node (ref "U1") (pin "16") (pinfunction "IO13_16") (pintype "bidirectional"))
    )
    (net (code "128") (name "unconnected-(U1-IO15-Pad23)") (class "Default")
      (node (ref "U1") (pin "23") (pinfunction "IO15_23") (pintype "bidirectional"))
    )
    (net (code "129") (name "unconnected-(U1-IO16-Pad27)") (class "Default")
      (node (ref "U1") (pin "27") (pinfunction "IO16_27") (pintype "bidirectional"))
    )
    (net (code "130") (name "unconnected-(U1-IO17-Pad28)") (class "Default")
      (node (ref "U1") (pin "28") (pinfunction "IO17_28") (pintype "bidirectional"))
    )
    (net (code "131") (name "unconnected-(U1-IO19-Pad31)") (class "Default")
      (node (ref "U1") (pin "31") (pinfunction "IO19_31") (pintype "bidirectional"))
    )
    (net (code "132") (name "unconnected-(U1-IO32-Pad8)") (class "Default")
      (node (ref "U1") (pin "8") (pinfunction "IO32_8") (pintype "bidirectional"))
    )
    (net (code "133") (name "unconnected-(U1-IO34-Pad6)") (class "Default")
      (node (ref "U1") (pin "6") (pinfunction "IO34_6") (pintype "bidirectional"))
    )
    (net (code "134") (name "unconnected-(U1-IO35-Pad7)") (class "Default")
      (node (ref "U1") (pin "7") (pinfunction "IO35_7") (pintype "bidirectional"))
    )
    (net (code "135") (name "unconnected-(U1-SD0-Pad21)") (class "Default")
      (node (ref "U1") (pin "21") (pinfunction "SD0_21") (pintype "bidirectional"))
    )
    (net (code "136") (name "unconnected-(U1-SD1-Pad22)") (class "Default")
      (node (ref "U1") (pin "22") (pinfunction "SD1_22") (pintype "bidirectional"))
    )
    (net (code "137") (name "unconnected-(U1-SD2-Pad17)") (class "Default")
      (node (ref "U1") (pin "17") (pinfunction "SD2_17") (pintype "bidirectional"))
    )
    (net (code "138") (name "unconnected-(U1-SD3-Pad18)") (class "Default")
      (node (ref "U1") (pin "18") (pinfunction "SD3_18") (pintype "bidirectional"))
    )
    (net (code "139") (name "unconnected-(U1-SVN-Pad5)") (class "Default")
      (node (ref "U1") (pin "5") (pinfunction "SVN_5") (pintype "bidirectional"))
    )
    (net (code "140") (name "unconnected-(U1-SVP-Pad4)") (class "Default")
      (node (ref "U1") (pin "4") (pinfunction "SVP_4") (pintype "bidirectional"))
    )
    (net (code "141") (name "unconnected-(U4-PA02-Pad18)") (class "Default")
      (node (ref "U4") (pin "18") (pinfunction "PA02_18") (pintype "bidirectional"))
    )
    (net (code "142") (name "unconnected-(U4-PA03-Pad19)") (class "Default")
      (node (ref "U4") (pin "19") (pinfunction "PA03_19") (pintype "bidirectional"))
    )
    (net (code "143") (name "unconnected-(U4-PA04-Pad20)") (class "Default")
      (node (ref "U4") (pin "20") (pinfunction "PA04_20") (pintype "bidirectional"))
    )
    (net (code "144") (name "unconnected-(U4-PA05-Pad1)") (class "Default")
      (node (ref "U4") (pin "1") (pinfunction "PA05_1") (pintype "bidirectional"))
    )
    (net (code "145") (name "unconnected-(U4-PA06-Pad2)") (class "Default")
      (node (ref "U4") (pin "2") (pinfunction "PA06_2") (pintype "bidirectional"))
    )
    (net (code "146") (name "unconnected-(U4-PA07-Pad3)") (class "Default")
      (node (ref "U4") (pin "3") (pinfunction "PA07_3") (pintype "bidirectional"))
    )
    (net (code "147") (name "unconnected-(U4-PA08{slash}XIN32-Pad4)") (class "Default")
      (node (ref "U4") (pin "4") (pinfunction "PA08/XIN32_4") (pintype "input"))
    )
    (net (code "148") (name "unconnected-(U4-PA09{slash}XOUT32-Pad5)") (class "Default")
      (node (ref "U4") (pin "5") (pinfunction "PA09/XOUT32_5") (pintype "input"))
    )
    (net (code "149") (name "unconnected-(U4-PA16-Pad8)") (class "Default")
      (node (ref "U4") (pin "8") (pinfunction "PA16_8") (pintype "bidirectional"))
    )
    (net (code "150") (name "unconnected-(U6-4A-Pad9)") (class "Default")
      (node (ref "U6") (pin "9") (pinfunction "4A_9") (pintype "bidirectional"))
    )
    (net (code "151") (name "unconnected-(U6-4Y-Pad10)") (class "Default")
      (node (ref "U6") (pin "10") (pinfunction "4Y_10") (pintype "bidirectional"))
    )
  )
)
